# OpenBookReader_v54.net
KiCad netlist of a schematic drawn in EAGLE
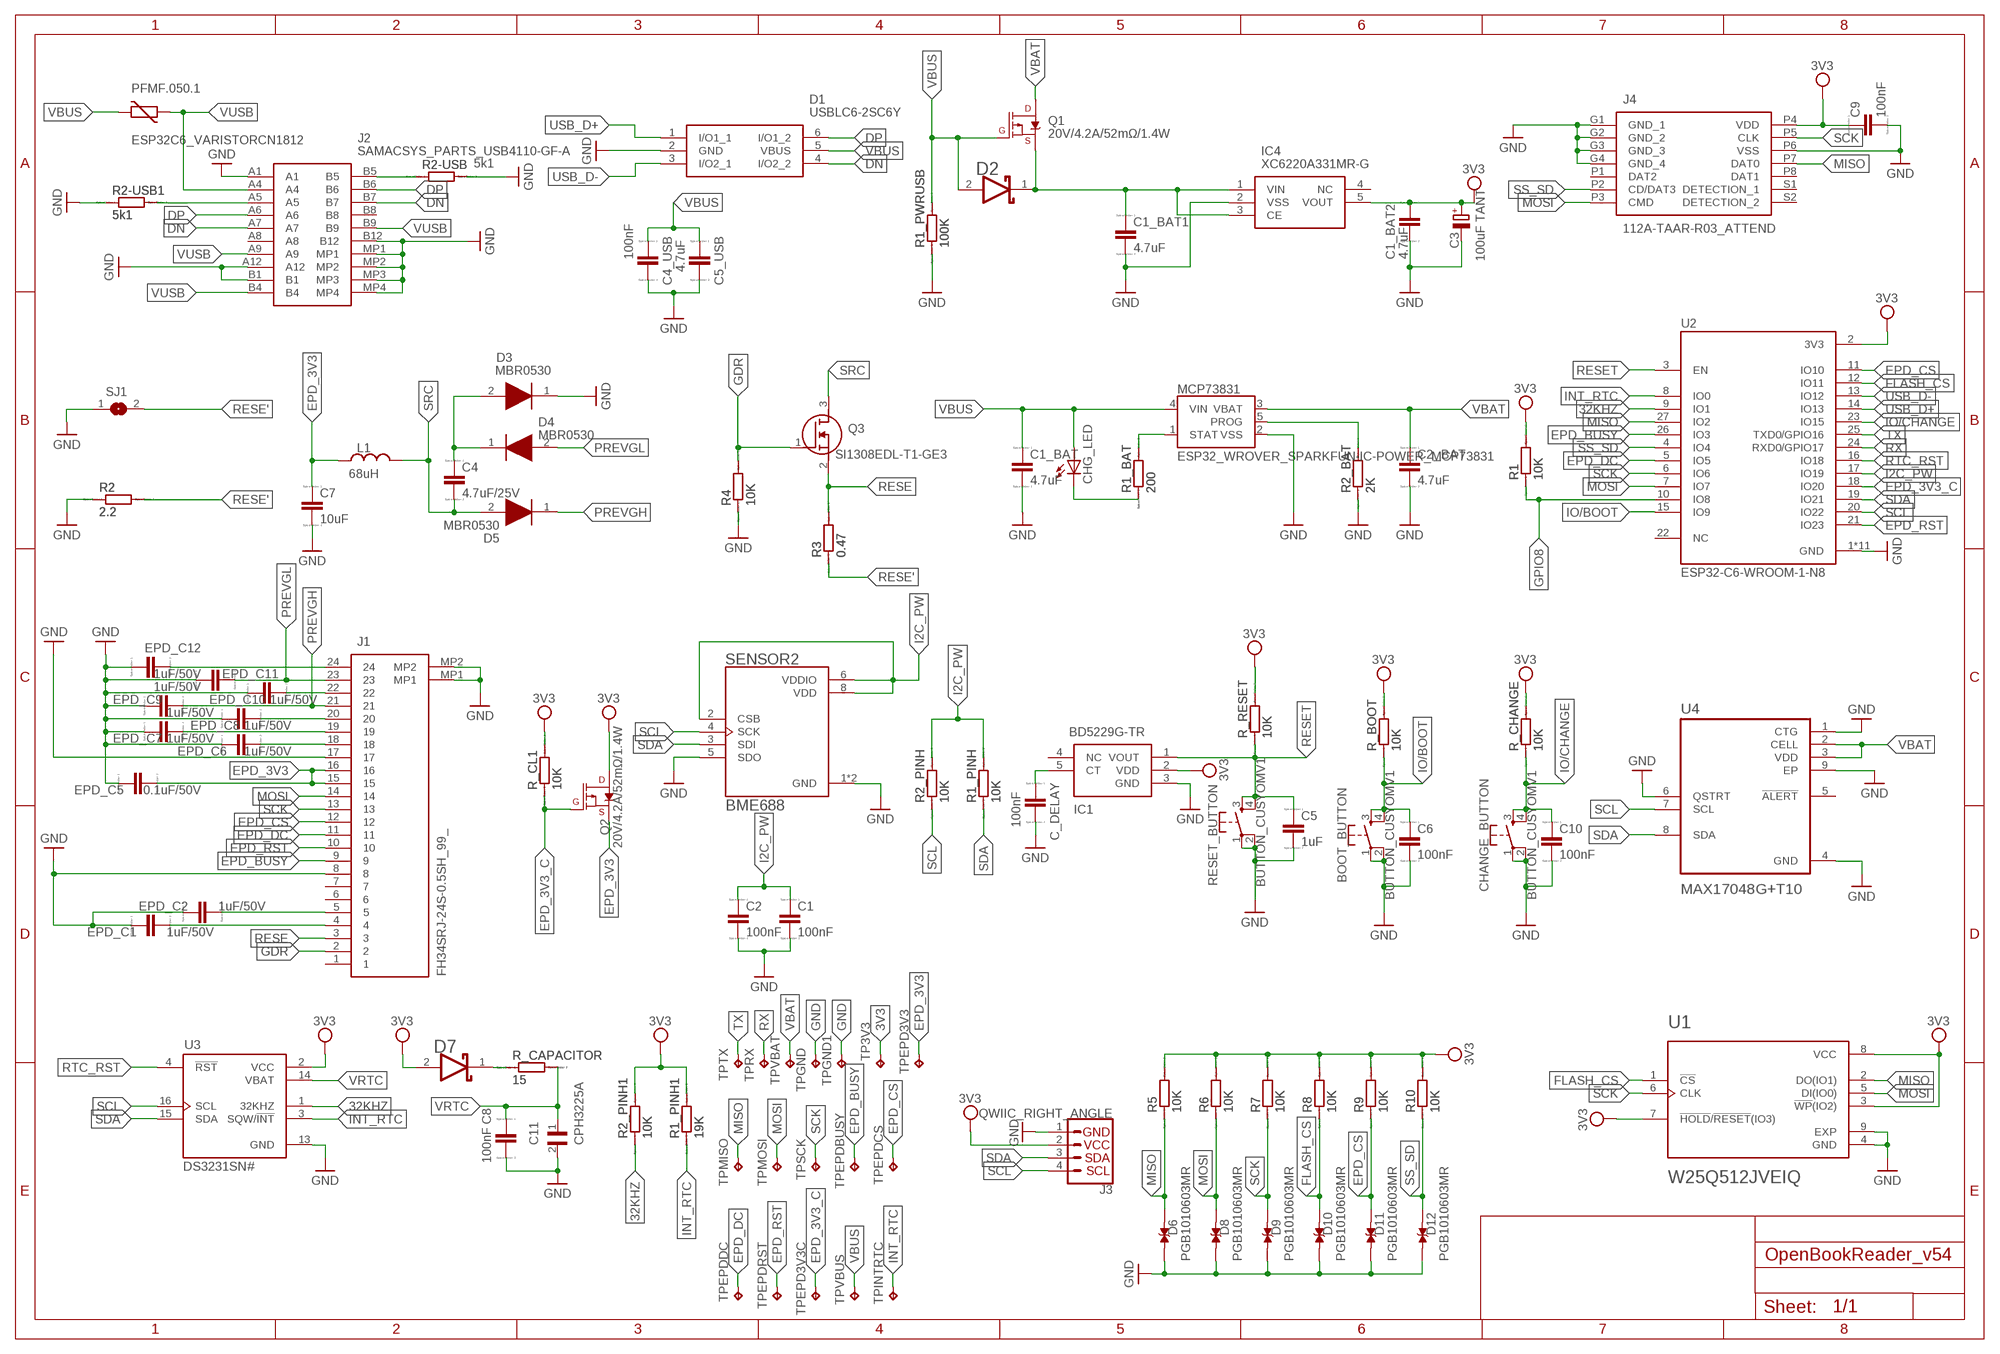
[diagram p0: schematic, sheet 1]

(export (version "E")
  (design (tool "Eeschema 10.0.6"))
  (components
    (comp (ref "BOOT_BUTTON")
      (value "BUTTON_CUSYOMV1")
      (footprint "eagle-import:MYBUTTON")
      (libsource (lib "eagle-import") (part "BUTTON_CUSYOMV1"))
    )
    (comp (ref "C1")
      (value "100nF")
      (footprint "eagle-import:EAGLE-LTSPICE_C0402")
      (libsource (lib "eagle-import") (part "EAGLE-LTSPICE_CC0402"))
    )
    (comp (ref "C1_BAT")
      (value "4.7uF")
      (footprint "eagle-import:EAGLE-LTSPICE_C0402")
      (libsource (lib "eagle-import") (part "EAGLE-LTSPICE_CC0402"))
    )
    (comp (ref "C1_BAT1")
      (value "4.7uF")
      (footprint "eagle-import:EAGLE-LTSPICE_C0402")
      (libsource (lib "eagle-import") (part "EAGLE-LTSPICE_CC0402"))
    )
    (comp (ref "C1_BAT2")
      (value "4.7uF")
      (footprint "eagle-import:EAGLE-LTSPICE_C0402")
      (libsource (lib "eagle-import") (part "EAGLE-LTSPICE_CC0402"))
    )
    (comp (ref "C2")
      (value "100nF")
      (footprint "eagle-import:EAGLE-LTSPICE_C0402")
      (libsource (lib "eagle-import") (part "EAGLE-LTSPICE_CC0402"))
    )
    (comp (ref "C2_BAT")
      (value "4.7uF")
      (footprint "eagle-import:EAGLE-LTSPICE_C0402")
      (libsource (lib "eagle-import") (part "EAGLE-LTSPICE_CC0402"))
    )
    (comp (ref "C3")
      (value "100uF TANT")
      (footprint "eagle-import:RCL_CT3528")
      (libsource (lib "eagle-import") (part "RCL_CPOL-EUCT3528"))
    )
    (comp (ref "C4")
      (value "4.7uF/25V")
      (footprint "eagle-import:EAGLE-LTSPICE_C0402")
      (libsource (lib "eagle-import") (part "EAGLE-LTSPICE_CC0402"))
    )
    (comp (ref "C4_USB")
      (value "100nF")
      (footprint "eagle-import:EAGLE-LTSPICE_C0402")
      (libsource (lib "eagle-import") (part "EAGLE-LTSPICE_CC0402"))
    )
    (comp (ref "C5")
      (value "1uF")
      (footprint "eagle-import:EAGLE-LTSPICE_C0402")
      (libsource (lib "eagle-import") (part "EAGLE-LTSPICE_CC0402"))
    )
    (comp (ref "C5_USB")
      (value "4.7uF")
      (footprint "eagle-import:EAGLE-LTSPICE_C0402")
      (libsource (lib "eagle-import") (part "EAGLE-LTSPICE_CC0402"))
    )
    (comp (ref "C6")
      (value "100nF")
      (footprint "eagle-import:EAGLE-LTSPICE_C0402")
      (libsource (lib "eagle-import") (part "EAGLE-LTSPICE_CC0402"))
    )
    (comp (ref "C7")
      (value "10uF")
      (footprint "eagle-import:EAGLE-LTSPICE_C0402")
      (libsource (lib "eagle-import") (part "EAGLE-LTSPICE_CC0402"))
    )
    (comp (ref "C8")
      (value "100nF")
      (footprint "eagle-import:EAGLE-LTSPICE_C0402")
      (libsource (lib "eagle-import") (part "EAGLE-LTSPICE_CC0402"))
    )
    (comp (ref "C9")
      (value "100nF")
      (footprint "eagle-import:EAGLE-LTSPICE_C0402")
      (libsource (lib "eagle-import") (part "EAGLE-LTSPICE_CC0402"))
    )
    (comp (ref "C10")
      (value "100nF")
      (footprint "eagle-import:EAGLE-LTSPICE_C0402")
      (libsource (lib "eagle-import") (part "EAGLE-LTSPICE_CC0402"))
    )
    (comp (ref "C11")
      (value "CPH3225A")
      (footprint "eagle-import:CAPCP3225X100N")
      (fields (field (name "MF") "Seiko Instruments"))
      (libsource (lib "eagle-import") (part "CPH3225A"))
    )
    (comp (ref "CHANGE_BUTTON")
      (value "BUTTON_CUSYOMV1")
      (footprint "eagle-import:MYBUTTON")
      (libsource (lib "eagle-import") (part "BUTTON_CUSYOMV1"))
    )
    (comp (ref "CHG_LED")
      (value "ADAFRUIT_LEDCHIP-LED0603")
      (footprint "eagle-import:ADAFRUIT_CHIP-LED0603")
      (libsource (lib "eagle-import") (part "ADAFRUIT_LEDCHIP-LED0603"))
    )
    (comp (ref "C_DELAY")
      (value "100nF")
      (footprint "eagle-import:EAGLE-LTSPICE_C0402")
      (libsource (lib "eagle-import") (part "EAGLE-LTSPICE_CC0402"))
    )
    (comp (ref "D1")
      (value "USBLC6-2SC6Y")
      (footprint "eagle-import:SOT95P280X145-6N")
      (fields (field (name "MF") "STMicroelectronics"))
      (libsource (lib "eagle-import") (part "USBLC6-2SC6Y"))
    )
    (comp (ref "D2")
      (value "ESP32_WROVER_AVX---SD0805S020S1R0_AVX_SD0805S020S1R0_0_0AVX_SD0805S020S1R0_0_0")
      (footprint "eagle-import:ESP32_WROVER_AVX---SD0805S020S1R0_AVX_SD0805S020S1R0_0")
      (fields
        (field (name "DIGIKEY_PART_NUMBER") "478-7800-1-ND")
        (field (name "MF") "AVX")
        (field (name "MOUSER_PART_NUMBER") "581-SD0805S020S1R0")
      )
      (libsource (lib "eagle-import") (part "ESP32_WROVER_AVX---SD0805S020S1R0_AVX_SD0805S020S1R0_0_0AVX_SD0805S020S1R0_0_0"))
    )
    (comp (ref "D3")
      (value "MBR0530")
      (footprint "eagle-import:SOD3716X135N")
      (fields (field (name "MF") "ON Semiconductor"))
      (libsource (lib "eagle-import") (part "MBR0530"))
    )
    (comp (ref "D4")
      (value "MBR0530")
      (footprint "eagle-import:SOD3716X135N")
      (fields (field (name "MF") "ON Semiconductor"))
      (libsource (lib "eagle-import") (part "MBR0530"))
    )
    (comp (ref "D5")
      (value "MBR0530")
      (footprint "eagle-import:SOD3716X135N")
      (fields (field (name "MF") "ON Semiconductor"))
      (libsource (lib "eagle-import") (part "MBR0530"))
    )
    (comp (ref "D6")
      (value "PGB1010603MR")
      (footprint "eagle-import:DIOC1608X36N")
      (fields (field (name "MF") "Littelfuse Inc."))
      (libsource (lib "eagle-import") (part "PGB1010603MR"))
    )
    (comp (ref "D7")
      (value "ESP32_WROVER_AVX---SD0805S020S1R0_AVX_SD0805S020S1R0_0_0AVX_SD0805S020S1R0_0_0")
      (footprint "eagle-import:ESP32_WROVER_AVX---SD0805S020S1R0_AVX_SD0805S020S1R0_0")
      (fields
        (field (name "DIGIKEY_PART_NUMBER") "478-7800-1-ND")
        (field (name "MF") "AVX")
        (field (name "MOUSER_PART_NUMBER") "581-SD0805S020S1R0")
      )
      (libsource (lib "eagle-import") (part "ESP32_WROVER_AVX---SD0805S020S1R0_AVX_SD0805S020S1R0_0_0AVX_SD0805S020S1R0_0_0"))
    )
    (comp (ref "D8")
      (value "PGB1010603MR")
      (footprint "eagle-import:DIOC1608X36N")
      (fields (field (name "MF") "Littelfuse Inc."))
      (libsource (lib "eagle-import") (part "PGB1010603MR"))
    )
    (comp (ref "D9")
      (value "PGB1010603MR")
      (footprint "eagle-import:DIOC1608X36N")
      (fields (field (name "MF") "Littelfuse Inc."))
      (libsource (lib "eagle-import") (part "PGB1010603MR"))
    )
    (comp (ref "D10")
      (value "PGB1010603MR")
      (footprint "eagle-import:DIOC1608X36N")
      (fields (field (name "MF") "Littelfuse Inc."))
      (libsource (lib "eagle-import") (part "PGB1010603MR"))
    )
    (comp (ref "D11")
      (value "PGB1010603MR")
      (footprint "eagle-import:DIOC1608X36N")
      (fields (field (name "MF") "Littelfuse Inc."))
      (libsource (lib "eagle-import") (part "PGB1010603MR"))
    )
    (comp (ref "D12")
      (value "PGB1010603MR")
      (footprint "eagle-import:DIOC1608X36N")
      (fields (field (name "MF") "Littelfuse Inc."))
      (libsource (lib "eagle-import") (part "PGB1010603MR"))
    )
    (comp (ref "EPD_C1")
      (value "1uF/50V")
      (footprint "eagle-import:EAGLE-LTSPICE_C0402")
      (libsource (lib "eagle-import") (part "EAGLE-LTSPICE_CC0402"))
    )
    (comp (ref "EPD_C2")
      (value "1uF/50V")
      (footprint "eagle-import:EAGLE-LTSPICE_C0402")
      (libsource (lib "eagle-import") (part "EAGLE-LTSPICE_CC0402"))
    )
    (comp (ref "EPD_C5")
      (value "0.1uF/50V")
      (footprint "eagle-import:EAGLE-LTSPICE_C0402")
      (libsource (lib "eagle-import") (part "EAGLE-LTSPICE_CC0402"))
    )
    (comp (ref "EPD_C6")
      (value "1uF/50V")
      (footprint "eagle-import:EAGLE-LTSPICE_C0402")
      (libsource (lib "eagle-import") (part "EAGLE-LTSPICE_CC0402"))
    )
    (comp (ref "EPD_C7")
      (value "1uF/50V")
      (footprint "eagle-import:EAGLE-LTSPICE_C0402")
      (libsource (lib "eagle-import") (part "EAGLE-LTSPICE_CC0402"))
    )
    (comp (ref "EPD_C8")
      (value "1uF/50V")
      (footprint "eagle-import:EAGLE-LTSPICE_C0402")
      (libsource (lib "eagle-import") (part "EAGLE-LTSPICE_CC0402"))
    )
    (comp (ref "EPD_C9")
      (value "1uF/50V")
      (footprint "eagle-import:EAGLE-LTSPICE_C0402")
      (libsource (lib "eagle-import") (part "EAGLE-LTSPICE_CC0402"))
    )
    (comp (ref "EPD_C10")
      (value "1uF/50V")
      (footprint "eagle-import:EAGLE-LTSPICE_C0402")
      (libsource (lib "eagle-import") (part "EAGLE-LTSPICE_CC0402"))
    )
    (comp (ref "EPD_C11")
      (value "1uF/50V")
      (footprint "eagle-import:EAGLE-LTSPICE_C0402")
      (libsource (lib "eagle-import") (part "EAGLE-LTSPICE_CC0402"))
    )
    (comp (ref "EPD_C12")
      (value "1uF/50V")
      (footprint "eagle-import:EAGLE-LTSPICE_C0402")
      (libsource (lib "eagle-import") (part "EAGLE-LTSPICE_CC0402"))
    )
    (comp (ref "IC1")
      (value "BD5229G-TR")
      (footprint "eagle-import:SOT95P280X125-5N")
      (fields (field (name "MOUSER_PART_NUMBER") "755-BD5229G-TR"))
      (libsource (lib "eagle-import") (part "BD5229G-TR"))
    )
    (comp (ref "IC4")
      (value "XC6220A331MR-G")
      (footprint "eagle-import:SOT95P280X120-5N")
      (fields (field (name "MOUSER_PART_NUMBER") "865-XC6220A331MR-G"))
      (libsource (lib "eagle-import") (part "XC6220A331MR-G"))
    )
    (comp (ref "J1")
      (value "FH34SRJ-24S-0.5SH_99_")
      (footprint "eagle-import:FH34SRJ24S05SH99")
      (fields
        (field (name "MANUFACTURER_PART_NUMBER") "FH34SRJ-24S-0.5SH(99)")
        (field (name "MOUSER_PART_NUMBER") "798-FH34SRJ24S05SH99")
      )
      (libsource (lib "eagle-import") (part "FH34SRJ-24S-0.5SH_99_"))
    )
    (comp (ref "J2")
      (value "SAMACSYS_PARTS_USB4110-GF-A")
      (footprint "eagle-import:SAMACSYS_PARTS_USB4110GFA")
      (fields
        (field (name "MANUFACTURER_PART_NUMBER") "USB4110-GF-A")
        (field (name "MOUSER_PART_NUMBER") "640-USB4110-GF-A")
      )
      (libsource (lib "eagle-import") (part "SAMACSYS_PARTS_USB4110-GF-A"))
    )
    (comp (ref "J3")
      (value "QWIIC_RIGHT_ANGLE")
      (footprint "eagle-import:JST04_1MM_RA")
      (libsource (lib "eagle-import") (part "QWIIC_CONNECTORJS-1MM"))
    )
    (comp (ref "J4")
      (value "112A-TAAR-R03_ATTEND")
      (footprint "eagle-import:112ATAARR03ATTEND")
      (fields (field (name "MANUFACTURER_PART_NUMBER") "112A-TAAR-R03 ATTEND"))
      (libsource (lib "eagle-import") (part "112A-TAAR-R03_ATTEND"))
    )
    (comp (ref "L1")
      (value "68uH")
      (footprint "eagle-import:INDC1006X60N")
      (libsource (lib "eagle-import") (part "INDUCTORCHIP-0402(1006-METRIC)_"))
    )
    (comp (ref "MCP73831")
      (value "ESP32_WROVER_SPARKFUN-IC-POWER_MCP73831")
      (footprint "eagle-import:ESP32_WROVER_SPARKFUN-IC-POWER_SOT23-5")
      (libsource (lib "eagle-import") (part "ESP32_WROVER_SPARKFUN-IC-POWER_MCP73831"))
    )
    (comp (ref "PFMF.050.1")
      (value "ESP32C6_VARISTORCN1812")
      (footprint "eagle-import:ESP32C6_VARISTOR_CT_CN1812")
      (libsource (lib "eagle-import") (part "ESP32C6_VARISTORCN1812"))
    )
    (comp (ref "Q1")
      (value "20V/4.2A/52mΩ/1.4W")
      (footprint "eagle-import:ESP32_WROVER_SPARKFUN-DISCRETESEMI_SOT23-3")
      (libsource (lib "eagle-import") (part "ESP32_WROVER_SPARKFUN-DISCRETESEMI_MOSFET_PCH-DMG2305UX-7"))
    )
    (comp (ref "Q2")
      (value "20V/4.2A/52mΩ/1.4W")
      (footprint "eagle-import:ESP32_WROVER_SPARKFUN-DISCRETESEMI_SOT23-3")
      (libsource (lib "eagle-import") (part "ESP32_WROVER_SPARKFUN-DISCRETESEMI_MOSFET_PCH-DMG2305UX-7"))
    )
    (comp (ref "Q3")
      (value "SI1308EDL-T1-GE3")
      (footprint "eagle-import:SOT65P210X110-3N")
      (fields (field (name "MF") "Vishay Siliconix"))
      (libsource (lib "eagle-import") (part "SI1308EDL-T1-GE3"))
    )
    (comp (ref "R1")
      (value "10K")
      (footprint "eagle-import:ESP32_WROVER_EAGLE-LTSPICE_R0402")
      (libsource (lib "eagle-import") (part "ESP32_WROVER_EAGLE-LTSPICE_RR0402"))
    )
    (comp (ref "R1_BAT")
      (value "200")
      (footprint "eagle-import:ESP32_WROVER_EAGLE-LTSPICE_R0402")
      (libsource (lib "eagle-import") (part "ESP32_WROVER_EAGLE-LTSPICE_RR0402"))
    )
    (comp (ref "R1_PINH")
      (value "10K")
      (footprint "eagle-import:ESP32_WROVER_EAGLE-LTSPICE_R0402")
      (libsource (lib "eagle-import") (part "ESP32_WROVER_EAGLE-LTSPICE_RR0402"))
    )
    (comp (ref "R1_PINH1")
      (value "19K")
      (footprint "eagle-import:ESP32_WROVER_EAGLE-LTSPICE_R0402")
      (libsource (lib "eagle-import") (part "ESP32_WROVER_EAGLE-LTSPICE_RR0402"))
    )
    (comp (ref "R1_PWRUSB")
      (value "100K")
      (footprint "eagle-import:ESP32_WROVER_EAGLE-LTSPICE_R0402")
      (libsource (lib "eagle-import") (part "ESP32_WROVER_EAGLE-LTSPICE_RR0402"))
    )
    (comp (ref "R2")
      (value "2.2")
      (footprint "eagle-import:ESP32_WROVER_EAGLE-LTSPICE_R0402")
      (libsource (lib "eagle-import") (part "ESP32_WROVER_EAGLE-LTSPICE_RR0402"))
    )
    (comp (ref "R2-USB")
      (value "5k1")
      (footprint "eagle-import:ESP32_WROVER_EAGLE-LTSPICE_R0402")
      (libsource (lib "eagle-import") (part "ESP32_WROVER_EAGLE-LTSPICE_RR0402"))
    )
    (comp (ref "R2-USB1")
      (value "5k1")
      (footprint "eagle-import:ESP32_WROVER_EAGLE-LTSPICE_R0402")
      (libsource (lib "eagle-import") (part "ESP32_WROVER_EAGLE-LTSPICE_RR0402"))
    )
    (comp (ref "R2_BAT")
      (value "2K")
      (footprint "eagle-import:ESP32_WROVER_EAGLE-LTSPICE_R0402")
      (libsource (lib "eagle-import") (part "ESP32_WROVER_EAGLE-LTSPICE_RR0402"))
    )
    (comp (ref "R2_PINH")
      (value "10K")
      (footprint "eagle-import:ESP32_WROVER_EAGLE-LTSPICE_R0402")
      (libsource (lib "eagle-import") (part "ESP32_WROVER_EAGLE-LTSPICE_RR0402"))
    )
    (comp (ref "R2_PINH1")
      (value "10K")
      (footprint "eagle-import:ESP32_WROVER_EAGLE-LTSPICE_R0402")
      (libsource (lib "eagle-import") (part "ESP32_WROVER_EAGLE-LTSPICE_RR0402"))
    )
    (comp (ref "R3")
      (value "0.47")
      (footprint "eagle-import:ESP32_WROVER_EAGLE-LTSPICE_R0402")
      (libsource (lib "eagle-import") (part "ESP32_WROVER_EAGLE-LTSPICE_RR0402"))
    )
    (comp (ref "R4")
      (value "10K")
      (footprint "eagle-import:ESP32_WROVER_EAGLE-LTSPICE_R0402")
      (libsource (lib "eagle-import") (part "ESP32_WROVER_EAGLE-LTSPICE_RR0402"))
    )
    (comp (ref "R5")
      (value "10K")
      (footprint "eagle-import:ESP32_WROVER_EAGLE-LTSPICE_R0402")
      (libsource (lib "eagle-import") (part "ESP32_WROVER_EAGLE-LTSPICE_RR0402"))
    )
    (comp (ref "R6")
      (value "10K")
      (footprint "eagle-import:ESP32_WROVER_EAGLE-LTSPICE_R0402")
      (libsource (lib "eagle-import") (part "ESP32_WROVER_EAGLE-LTSPICE_RR0402"))
    )
    (comp (ref "R7")
      (value "10K")
      (footprint "eagle-import:ESP32_WROVER_EAGLE-LTSPICE_R0402")
      (libsource (lib "eagle-import") (part "ESP32_WROVER_EAGLE-LTSPICE_RR0402"))
    )
    (comp (ref "R8")
      (value "10K")
      (footprint "eagle-import:ESP32_WROVER_EAGLE-LTSPICE_R0402")
      (libsource (lib "eagle-import") (part "ESP32_WROVER_EAGLE-LTSPICE_RR0402"))
    )
    (comp (ref "R9")
      (value "10K")
      (footprint "eagle-import:ESP32_WROVER_EAGLE-LTSPICE_R0402")
      (libsource (lib "eagle-import") (part "ESP32_WROVER_EAGLE-LTSPICE_RR0402"))
    )
    (comp (ref "R10")
      (value "10K")
      (footprint "eagle-import:ESP32_WROVER_EAGLE-LTSPICE_R0402")
      (libsource (lib "eagle-import") (part "ESP32_WROVER_EAGLE-LTSPICE_RR0402"))
    )
    (comp (ref "RESET_BUTTON")
      (value "BUTTON_CUSYOMV1")
      (footprint "eagle-import:MYBUTTON")
      (libsource (lib "eagle-import") (part "BUTTON_CUSYOMV1"))
    )
    (comp (ref "R_BOOT")
      (value "10K")
      (footprint "eagle-import:ESP32_WROVER_EAGLE-LTSPICE_R0402")
      (libsource (lib "eagle-import") (part "ESP32_WROVER_EAGLE-LTSPICE_RR0402"))
    )
    (comp (ref "R_CAPACITOR")
      (value "15")
      (footprint "eagle-import:ESP32_WROVER_EAGLE-LTSPICE_R0402")
      (libsource (lib "eagle-import") (part "ESP32_WROVER_EAGLE-LTSPICE_RR0402"))
    )
    (comp (ref "R_CHANGE")
      (value "10K")
      (footprint "eagle-import:ESP32_WROVER_EAGLE-LTSPICE_R0402")
      (libsource (lib "eagle-import") (part "ESP32_WROVER_EAGLE-LTSPICE_RR0402"))
    )
    (comp (ref "R_CL1")
      (value "10K")
      (footprint "eagle-import:ESP32_WROVER_EAGLE-LTSPICE_R0402")
      (libsource (lib "eagle-import") (part "ESP32_WROVER_EAGLE-LTSPICE_RR0402"))
    )
    (comp (ref "R_RESET")
      (value "10K")
      (footprint "eagle-import:ESP32_WROVER_EAGLE-LTSPICE_R0402")
      (libsource (lib "eagle-import") (part "ESP32_WROVER_EAGLE-LTSPICE_RR0402"))
    )
    (comp (ref "SENSOR2")
      (value "BME688")
      (footprint "eagle-import:ESP32_WROVER_BME680_PSON80P300X300X100-8N")
      (fields (field (name "MF") "Bosch Sensortec") (field (name "MP") "BME680"))
      (libsource (lib "eagle-import") (part "ESP32_WROVER_BME680_BME680"))
    )
    (comp (ref "SJ1") (value "SJ") (footprint "eagle-import:SJ") (libsource (lib "eagle-import") (part "SJ")))
    (comp (ref "TP3V3")
      (value "TPTP20R")
      (footprint "eagle-import:TP20R")
      (libsource (lib "eagle-import") (part "TPTP20R"))
    )
    (comp (ref "TPEPD3V3")
      (value "TPTP20R")
      (footprint "eagle-import:TP20R")
      (libsource (lib "eagle-import") (part "TPTP20R"))
    )
    (comp (ref "TPEPD3V3C")
      (value "TPTP20R")
      (footprint "eagle-import:TP20R")
      (libsource (lib "eagle-import") (part "TPTP20R"))
    )
    (comp (ref "TPEPDBUSY")
      (value "TPTP20R")
      (footprint "eagle-import:TP20R")
      (libsource (lib "eagle-import") (part "TPTP20R"))
    )
    (comp (ref "TPEPDCS")
      (value "TPTP20R")
      (footprint "eagle-import:TP20R")
      (libsource (lib "eagle-import") (part "TPTP20R"))
    )
    (comp (ref "TPEPDDC")
      (value "TPTP20R")
      (footprint "eagle-import:TP20R")
      (libsource (lib "eagle-import") (part "TPTP20R"))
    )
    (comp (ref "TPEPDRST")
      (value "TPTP20R")
      (footprint "eagle-import:TP20R")
      (libsource (lib "eagle-import") (part "TPTP20R"))
    )
    (comp (ref "TPGND")
      (value "TPTP20R")
      (footprint "eagle-import:TP20R")
      (libsource (lib "eagle-import") (part "TPTP20R"))
    )
    (comp (ref "TPGND1")
      (value "TPTP20R")
      (footprint "eagle-import:TP20R")
      (libsource (lib "eagle-import") (part "TPTP20R"))
    )
    (comp (ref "TPINTRTC")
      (value "TPTP20R")
      (footprint "eagle-import:TP20R")
      (libsource (lib "eagle-import") (part "TPTP20R"))
    )
    (comp (ref "TPMISO")
      (value "TPTP20R")
      (footprint "eagle-import:TP20R")
      (libsource (lib "eagle-import") (part "TPTP20R"))
    )
    (comp (ref "TPMOSI")
      (value "TPTP20R")
      (footprint "eagle-import:TP20R")
      (libsource (lib "eagle-import") (part "TPTP20R"))
    )
    (comp (ref "TPRX")
      (value "TPTP20R")
      (footprint "eagle-import:TP20R")
      (libsource (lib "eagle-import") (part "TPTP20R"))
    )
    (comp (ref "TPSCK")
      (value "TPTP20R")
      (footprint "eagle-import:TP20R")
      (libsource (lib "eagle-import") (part "TPTP20R"))
    )
    (comp (ref "TPTX")
      (value "TPTP20R")
      (footprint "eagle-import:TP20R")
      (libsource (lib "eagle-import") (part "TPTP20R"))
    )
    (comp (ref "TPVBAT")
      (value "TPTP20R")
      (footprint "eagle-import:TP20R")
      (libsource (lib "eagle-import") (part "TPTP20R"))
    )
    (comp (ref "TPVBUS")
      (value "TPTP20R")
      (footprint "eagle-import:TP20R")
      (libsource (lib "eagle-import") (part "TPTP20R"))
    )
    (comp (ref "U1")
      (value "W25Q512JVEIQ")
      (footprint "eagle-import:SON127P600X800X80-9N")
      (fields (field (name "MF") "Winbond Electronics"))
      (libsource (lib "eagle-import") (part "W25Q512JVEIQ"))
    )
    (comp (ref "U2")
      (value "ESP32-C6-WROOM-1-N8")
      (footprint "eagle-import:XCVR_ESP32-C6-WROOM-1-N8")
      (fields (field (name "MF") "Espressif Systems"))
      (libsource (lib "eagle-import") (part "ESP32-C6-WROOM-1-N8"))
    )
    (comp (ref "U3")
      (value "DS3231SN#")
      (footprint "eagle-import:SOIC127P1032X265-16N")
      (fields (field (name "MF") "Analog Devices"))
      (libsource (lib "eagle-import") (part "DS3231SN#"))
    )
    (comp (ref "U4")
      (value "MAX17048G+T10")
      (footprint "eagle-import:SON50P200X200X80-9N")
      (fields (field (name "MF") "Analog Devices"))
      (libsource (lib "eagle-import") (part "MAX17048G+T10"))
    )
  )
  (nets
    (net (code "1") (name "3V3") (class "Default")
      (node (ref "C1_BAT2") (pin "1") (pinfunction "1_1") (pintype "passive"))
      (node (ref "C3") (pin "+") (pinfunction "+_+") (pintype "passive"))
      (node (ref "C9") (pin "1") (pinfunction "1_1") (pintype "passive"))
      (node (ref "D7") (pin "2") (pinfunction "ANODE_2") (pintype "bidirectional"))
      (node (ref "IC1") (pin "2") (pinfunction "VDD_2") (pintype "bidirectional"))
      (node (ref "IC4") (pin "5") (pinfunction "VOUT_5") (pintype "bidirectional"))
      (node (ref "J3") (pin "2") (pinfunction "2_2") (pintype "power_in"))
      (node (ref "J4") (pin "P4") (pinfunction "VDD_P4") (pintype "bidirectional"))
      (node (ref "Q2") (pin "3") (pinfunction "D_3") (pintype "bidirectional"))
      (node (ref "R1") (pin "2") (pinfunction "2_2") (pintype "passive"))
      (node (ref "R10") (pin "2") (pinfunction "2_2") (pintype "passive"))
      (node (ref "R1_PINH1") (pin "2") (pinfunction "2_2") (pintype "passive"))
      (node (ref "R2_PINH1") (pin "2") (pinfunction "2_2") (pintype "passive"))
      (node (ref "R5") (pin "2") (pinfunction "2_2") (pintype "passive"))
      (node (ref "R6") (pin "2") (pinfunction "2_2") (pintype "passive"))
      (node (ref "R7") (pin "2") (pinfunction "2_2") (pintype "passive"))
      (node (ref "R8") (pin "2") (pinfunction "2_2") (pintype "passive"))
      (node (ref "R9") (pin "2") (pinfunction "2_2") (pintype "passive"))
      (node (ref "R_BOOT") (pin "2") (pinfunction "2_2") (pintype "passive"))
      (node (ref "R_CHANGE") (pin "2") (pinfunction "2_2") (pintype "passive"))
      (node (ref "R_CL1") (pin "2") (pinfunction "2_2") (pintype "passive"))
      (node (ref "R_RESET") (pin "2") (pinfunction "2_2") (pintype "passive"))
      (node (ref "TP3V3") (pin "TP") (pinfunction "TP_TP") (pintype "input"))
      (node (ref "U1") (pin "3") (pinfunction "~{WP}(IO2)_3") (pintype "bidirectional"))
      (node (ref "U1") (pin "7") (pinfunction "~{HOLD}/~{RESET}(IO3)_7") (pintype "bidirectional"))
      (node (ref "U1") (pin "8") (pinfunction "VCC_8") (pintype "power_in"))
      (node (ref "U2") (pin "2") (pinfunction "3V3_2") (pintype "power_in"))
      (node (ref "U3") (pin "2") (pinfunction "VCC_2") (pintype "power_in"))
    )
    (net (code "2") (name "32KHZ") (class "Default")
      (node (ref "R2_PINH1") (pin "1") (pinfunction "1_1") (pintype "passive"))
      (node (ref "U2") (pin "9") (pinfunction "IO1_9") (pintype "bidirectional"))
      (node (ref "U3") (pin "1") (pinfunction "32KHZ_1") (pintype "output"))
    )
    (net (code "3") (name "DN") (class "Default")
      (node (ref "D1") (pin "4") (pinfunction "I/O2_2_4") (pintype "bidirectional"))
      (node (ref "J2") (pin "A7") (pinfunction "A7_A7") (pintype "bidirectional"))
      (node (ref "J2") (pin "B7") (pinfunction "B7_B7") (pintype "bidirectional"))
    )
    (net (code "4") (name "DP") (class "Default")
      (node (ref "D1") (pin "6") (pinfunction "I/O1_2_6") (pintype "bidirectional"))
      (node (ref "J2") (pin "A6") (pinfunction "A6_A6") (pintype "bidirectional"))
      (node (ref "J2") (pin "B6") (pinfunction "B6_B6") (pintype "bidirectional"))
    )
    (net (code "5") (name "EPD_3V3") (class "Default")
      (node (ref "C7") (pin "1") (pinfunction "1_1") (pintype "passive"))
      (node (ref "EPD_C5") (pin "2") (pinfunction "2_2") (pintype "passive"))
      (node (ref "J1") (pin "15") (pinfunction "15_15") (pintype "bidirectional"))
      (node (ref "J1") (pin "16") (pinfunction "16_16") (pintype "bidirectional"))
      (node (ref "L1") (pin "1") (pinfunction "1_1") (pintype "passive"))
      (node (ref "Q2") (pin "2") (pinfunction "S_2") (pintype "bidirectional"))
      (node (ref "TPEPD3V3") (pin "TP") (pinfunction "TP_TP") (pintype "input"))
    )
    (net (code "6") (name "EPD_3V3_C") (class "Default")
      (node (ref "Q2") (pin "1") (pinfunction "G_1") (pintype "bidirectional"))
      (node (ref "R_CL1") (pin "1") (pinfunction "1_1") (pintype "passive"))
      (node (ref "TPEPD3V3C") (pin "TP") (pinfunction "TP_TP") (pintype "input"))
      (node (ref "U2") (pin "18") (pinfunction "IO20_18") (pintype "bidirectional"))
    )
    (net (code "7") (name "EPD_BUSY") (class "Default")
      (node (ref "J1") (pin "9") (pinfunction "9_9") (pintype "bidirectional"))
      (node (ref "TPEPDBUSY") (pin "TP") (pinfunction "TP_TP") (pintype "input"))
      (node (ref "U2") (pin "26") (pinfunction "IO3_26") (pintype "bidirectional"))
    )
    (net (code "8") (name "EPD_CS") (class "Default")
      (node (ref "D11") (pin "2") (pinfunction "2_2") (pintype "passive"))
      (node (ref "J1") (pin "12") (pinfunction "12_12") (pintype "bidirectional"))
      (node (ref "R9") (pin "1") (pinfunction "1_1") (pintype "passive"))
      (node (ref "TPEPDCS") (pin "TP") (pinfunction "TP_TP") (pintype "input"))
      (node (ref "U2") (pin "11") (pinfunction "IO10_11") (pintype "bidirectional"))
    )
    (net (code "9") (name "EPD_DC") (class "Default")
      (node (ref "J1") (pin "11") (pinfunction "11_11") (pintype "bidirectional"))
      (node (ref "TPEPDDC") (pin "TP") (pinfunction "TP_TP") (pintype "input"))
      (node (ref "U2") (pin "5") (pinfunction "IO5_5") (pintype "bidirectional"))
    )
    (net (code "10") (name "EPD_RST") (class "Default")
      (node (ref "J1") (pin "10") (pinfunction "10_10") (pintype "bidirectional"))
      (node (ref "TPEPDRST") (pin "TP") (pinfunction "TP_TP") (pintype "input"))
      (node (ref "U2") (pin "21") (pinfunction "IO23_21") (pintype "bidirectional"))
    )
    (net (code "11") (name "FLASH_CS") (class "Default")
      (node (ref "D10") (pin "2") (pinfunction "2_2") (pintype "passive"))
      (node (ref "R8") (pin "1") (pinfunction "1_1") (pintype "passive"))
      (node (ref "U1") (pin "1") (pinfunction "~{CS}_1") (pintype "input"))
      (node (ref "U2") (pin "12") (pinfunction "IO11_12") (pintype "bidirectional"))
    )
    (net (code "12") (name "GDR") (class "Default")
      (node (ref "J1") (pin "2") (pinfunction "2_2") (pintype "bidirectional"))
      (node (ref "Q3") (pin "1") (pinfunction "G_1") (pintype "bidirectional"))
      (node (ref "R4") (pin "2") (pinfunction "2_2") (pintype "passive"))
    )
    (net (code "13") (name "GND") (class "Default")
      (node (ref "BOOT_BUTTON") (pin "1") (pinfunction "1_1") (pintype "passive"))
      (node (ref "BOOT_BUTTON") (pin "2") (pinfunction "2_2") (pintype "passive"))
      (node (ref "C1") (pin "2") (pinfunction "2_2") (pintype "passive"))
      (node (ref "C10") (pin "2") (pinfunction "2_2") (pintype "passive"))
      (node (ref "C11") (pin "2") (pinfunction "2_2") (pintype "passive"))
      (node (ref "C1_BAT") (pin "2") (pinfunction "2_2") (pintype "passive"))
      (node (ref "C1_BAT1") (pin "2") (pinfunction "2_2") (pintype "passive"))
      (node (ref "C1_BAT2") (pin "2") (pinfunction "2_2") (pintype "passive"))
      (node (ref "C2") (pin "2") (pinfunction "2_2") (pintype "passive"))
      (node (ref "C2_BAT") (pin "2") (pinfunction "2_2") (pintype "passive"))
      (node (ref "C3") (pin "-") (pinfunction "-_-") (pintype "passive"))
      (node (ref "C4_USB") (pin "2") (pinfunction "2_2") (pintype "passive"))
      (node (ref "C5") (pin "2") (pinfunction "2_2") (pintype "passive"))
      (node (ref "C5_USB") (pin "2") (pinfunction "2_2") (pintype "passive"))
      (node (ref "C6") (pin "2") (pinfunction "2_2") (pintype "passive"))
      (node (ref "C7") (pin "2") (pinfunction "2_2") (pintype "passive"))
      (node (ref "C8") (pin "2") (pinfunction "2_2") (pintype "passive"))
      (node (ref "C9") (pin "2") (pinfunction "2_2") (pintype "passive"))
      (node (ref "CHANGE_BUTTON") (pin "1") (pinfunction "1_1") (pintype "passive"))
      (node (ref "CHANGE_BUTTON") (pin "2") (pinfunction "2_2") (pintype "passive"))
      (node (ref "C_DELAY") (pin "2") (pinfunction "2_2") (pintype "passive"))
      (node (ref "D1") (pin "2") (pinfunction "GND_2") (pintype "bidirectional"))
      (node (ref "D10") (pin "1") (pinfunction "1_1") (pintype "passive"))
      (node (ref "D11") (pin "1") (pinfunction "1_1") (pintype "passive"))
      (node (ref "D12") (pin "1") (pinfunction "1_1") (pintype "passive"))
      (node (ref "D3") (pin "1") (pinfunction "K_1") (pintype "bidirectional"))
      (node (ref "D6") (pin "1") (pinfunction "1_1") (pintype "passive"))
      (node (ref "D8") (pin "1") (pinfunction "1_1") (pintype "passive"))
      (node (ref "D9") (pin "1") (pinfunction "1_1") (pintype "passive"))
      (node (ref "EPD_C1") (pin "1") (pinfunction "1_1") (pintype "passive"))
      (node (ref "EPD_C10") (pin "1") (pinfunction "1_1") (pintype "passive"))
      (node (ref "EPD_C11") (pin "1") (pinfunction "1_1") (pintype "passive"))
      (node (ref "EPD_C12") (pin "1") (pinfunction "1_1") (pintype "passive"))
      (node (ref "EPD_C2") (pin "1") (pinfunction "1_1") (pintype "passive"))
      (node (ref "EPD_C5") (pin "1") (pinfunction "1_1") (pintype "passive"))
      (node (ref "EPD_C6") (pin "1") (pinfunction "1_1") (pintype "passive"))
      (node (ref "EPD_C7") (pin "1") (pinfunction "1_1") (pintype "passive"))
      (node (ref "EPD_C8") (pin "1") (pinfunction "1_1") (pintype "passive"))
      (node (ref "EPD_C9") (pin "1") (pinfunction "1_1") (pintype "passive"))
      (node (ref "IC1") (pin "3") (pinfunction "GND_3") (pintype "bidirectional"))
      (node (ref "IC4") (pin "2") (pinfunction "VSS_2") (pintype "bidirectional"))
      (node (ref "J1") (pin "17") (pinfunction "17_17") (pintype "bidirectional"))
      (node (ref "J1") (pin "8") (pinfunction "8_8") (pintype "bidirectional"))
      (node (ref "J1") (pin "MP1") (pinfunction "MP1_MP1") (pintype "bidirectional"))
      (node (ref "J1") (pin "MP2") (pinfunction "MP2_MP2") (pintype "bidirectional"))
      (node (ref "J2") (pin "A1") (pinfunction "A1_A1") (pintype "bidirectional"))
      (node (ref "J2") (pin "A12") (pinfunction "A12_A12") (pintype "bidirectional"))
      (node (ref "J2") (pin "B1") (pinfunction "B1_B1") (pintype "bidirectional"))
      (node (ref "J2") (pin "B12") (pinfunction "B12_B12") (pintype "bidirectional"))
      (node (ref "J2") (pin "MP1") (pinfunction "MP1_MP1") (pintype "bidirectional"))
      (node (ref "J2") (pin "MP2") (pinfunction "MP2_MP2") (pintype "bidirectional"))
      (node (ref "J2") (pin "MP3") (pinfunction "MP3_MP3") (pintype "bidirectional"))
      (node (ref "J2") (pin "MP4") (pinfunction "MP4_MP4") (pintype "bidirectional"))
      (node (ref "J3") (pin "1") (pinfunction "1_1") (pintype "power_in"))
      (node (ref "J4") (pin "G1") (pinfunction "GND_1_G1") (pintype "bidirectional"))
      (node (ref "J4") (pin "G2") (pinfunction "GND_2_G2") (pintype "bidirectional"))
      (node (ref "J4") (pin "G3") (pinfunction "GND_3_G3") (pintype "bidirectional"))
      (node (ref "J4") (pin "G4") (pinfunction "GND_4_G4") (pintype "bidirectional"))
      (node (ref "J4") (pin "P6") (pinfunction "VSS_P6") (pintype "bidirectional"))
      (node (ref "MCP73831") (pin "2") (pinfunction "VSS_2") (pintype "power_in"))
      (node (ref "R1_PWRUSB") (pin "1") (pinfunction "1_1") (pintype "passive"))
      (node (ref "R2") (pin "1") (pinfunction "1_1") (pintype "passive"))
      (node (ref "R2-USB") (pin "2") (pinfunction "2_2") (pintype "passive"))
      (node (ref "R2-USB1") (pin "1") (pinfunction "1_1") (pintype "passive"))
      (node (ref "R2_BAT") (pin "1") (pinfunction "1_1") (pintype "passive"))
      (node (ref "R4") (pin "1") (pinfunction "1_1") (pintype "passive"))
      (node (ref "RESET_BUTTON") (pin "1") (pinfunction "1_1") (pintype "passive"))
      (node (ref "RESET_BUTTON") (pin "2") (pinfunction "2_2") (pintype "passive"))
      (node (ref "SENSOR2") (pin "1") (pinfunction "GND_1") (pintype "power_in"))
      (node (ref "SENSOR2") (pin "5") (pinfunction "SDO_5") (pintype "bidirectional"))
      (node (ref "SENSOR2") (pin "7") (pinfunction "GND_7") (pintype "power_in"))
      (node (ref "SJ1") (pin "1") (pinfunction "1_1") (pintype "passive"))
      (node (ref "TPGND") (pin "TP") (pinfunction "TP_TP") (pintype "input"))
      (node (ref "TPGND1") (pin "TP") (pinfunction "TP_TP") (pintype "input"))
      (node (ref "U1") (pin "4") (pinfunction "GND_4") (pintype "power_in"))
      (node (ref "U1") (pin "9") (pinfunction "EXP_9") (pintype "passive"))
      (node (ref "U2") (pin "1") (pinfunction "GND_1") (pintype "power_in"))
      (node (ref "U2") (pin "28") (pinfunction "GND_28") (pintype "power_in"))
      (node (ref "U2") (pin "29_1") (pinfunction "GND_29_1") (pintype "power_in"))
      (node (ref "U2") (pin "29_2") (pinfunction "GND_29_2") (pintype "power_in"))
      (node (ref "U2") (pin "29_3") (pinfunction "GND_29_3") (pintype "power_in"))
      (node (ref "U2") (pin "29_4") (pinfunction "GND_29_4") (pintype "power_in"))
      (node (ref "U2") (pin "29_5") (pinfunction "GND_29_5") (pintype "power_in"))
      (node (ref "U2") (pin "29_6") (pinfunction "GND_29_6") (pintype "power_in"))
      (node (ref "U2") (pin "29_7") (pinfunction "GND_29_7") (pintype "power_in"))
      (node (ref "U2") (pin "29_8") (pinfunction "GND_29_8") (pintype "power_in"))
      (node (ref "U2") (pin "29_9") (pinfunction "GND_29_9") (pintype "power_in"))
      (node (ref "U3") (pin "13") (pinfunction "GND_13") (pintype "power_in"))
      (node (ref "U4") (pin "1") (pinfunction "CTG_1") (pintype "power_in"))
      (node (ref "U4") (pin "4") (pinfunction "GND_4") (pintype "power_in"))
      (node (ref "U4") (pin "6") (pinfunction "QSTRT_6") (pintype "input"))
      (node (ref "U4") (pin "9") (pinfunction "EP_9") (pintype "power_in"))
    )
    (net (code "14") (name "GPIO8") (class "Default")
      (node (ref "R1") (pin "1") (pinfunction "1_1") (pintype "passive"))
      (node (ref "U2") (pin "10") (pinfunction "IO8_10") (pintype "bidirectional"))
    )
    (net (code "15") (name "I2C_PW") (class "Default")
      (node (ref "C1") (pin "1") (pinfunction "1_1") (pintype "passive"))
      (node (ref "C2") (pin "1") (pinfunction "1_1") (pintype "passive"))
      (node (ref "R1_PINH") (pin "2") (pinfunction "2_2") (pintype "passive"))
      (node (ref "R2_PINH") (pin "2") (pinfunction "2_2") (pintype "passive"))
      (node (ref "SENSOR2") (pin "2") (pinfunction "CSB_2") (pintype "input"))
      (node (ref "SENSOR2") (pin "6") (pinfunction "VDDIO_6") (pintype "power_in"))
      (node (ref "SENSOR2") (pin "8") (pinfunction "VDD_8") (pintype "power_in"))
      (node (ref "U2") (pin "17") (pinfunction "IO19_17") (pintype "bidirectional"))
    )
    (net (code "16") (name "INT_RTC") (class "Default")
      (node (ref "R1_PINH1") (pin "1") (pinfunction "1_1") (pintype "passive"))
      (node (ref "TPINTRTC") (pin "TP") (pinfunction "TP_TP") (pintype "input"))
      (node (ref "U2") (pin "8") (pinfunction "IO0_8") (pintype "bidirectional"))
      (node (ref "U3") (pin "3") (pinfunction "SQW/~{INT}_3") (pintype "output"))
    )
    (net (code "17") (name "IO{slash}BOOT") (class "Default")
      (node (ref "BOOT_BUTTON") (pin "3") (pinfunction "3_3") (pintype "passive"))
      (node (ref "BOOT_BUTTON") (pin "4") (pinfunction "4_4") (pintype "passive"))
      (node (ref "C6") (pin "1") (pinfunction "1_1") (pintype "passive"))
      (node (ref "R_BOOT") (pin "1") (pinfunction "1_1") (pintype "passive"))
      (node (ref "U2") (pin "15") (pinfunction "IO9_15") (pintype "bidirectional"))
    )
    (net (code "18") (name "IO{slash}CHANGE") (class "Default")
      (node (ref "C10") (pin "1") (pinfunction "1_1") (pintype "passive"))
      (node (ref "CHANGE_BUTTON") (pin "3") (pinfunction "3_3") (pintype "passive"))
      (node (ref "CHANGE_BUTTON") (pin "4") (pinfunction "4_4") (pintype "passive"))
      (node (ref "R_CHANGE") (pin "1") (pinfunction "1_1") (pintype "passive"))
      (node (ref "U2") (pin "23") (pinfunction "IO15_23") (pintype "bidirectional"))
    )
    (net (code "19") (name "MISO") (class "Default")
      (node (ref "D6") (pin "2") (pinfunction "2_2") (pintype "passive"))
      (node (ref "J4") (pin "P7") (pinfunction "DAT0_P7") (pintype "bidirectional"))
      (node (ref "R5") (pin "1") (pinfunction "1_1") (pintype "passive"))
      (node (ref "TPMISO") (pin "TP") (pinfunction "TP_TP") (pintype "input"))
      (node (ref "U1") (pin "2") (pinfunction "DO(IO1)_2") (pintype "bidirectional"))
      (node (ref "U2") (pin "27") (pinfunction "IO2_27") (pintype "bidirectional"))
    )
    (net (code "20") (name "MOSI") (class "Default")
      (node (ref "D8") (pin "2") (pinfunction "2_2") (pintype "passive"))
      (node (ref "J1") (pin "14") (pinfunction "14_14") (pintype "bidirectional"))
      (node (ref "J4") (pin "P3") (pinfunction "CMD_P3") (pintype "bidirectional"))
      (node (ref "R6") (pin "1") (pinfunction "1_1") (pintype "passive"))
      (node (ref "TPMOSI") (pin "TP") (pinfunction "TP_TP") (pintype "input"))
      (node (ref "U1") (pin "5") (pinfunction "DI(IO0)_5") (pintype "bidirectional"))
      (node (ref "U2") (pin "7") (pinfunction "IO7_7") (pintype "bidirectional"))
    )
    (net (code "21") (name "Net-(CHG_LED-PadC)") (class "Default")
      (node (ref "CHG_LED") (pin "C") (pinfunction "C_C") (pintype "passive"))
      (node (ref "R1_BAT") (pin "1") (pinfunction "1_1") (pintype "passive"))
    )
    (net (code "22") (name "Net-(D2-CATHODE)") (class "Default")
      (node (ref "C1_BAT1") (pin "1") (pinfunction "1_1") (pintype "passive"))
      (node (ref "D2") (pin "1") (pinfunction "CATHODE_1") (pintype "bidirectional"))
      (node (ref "IC4") (pin "1") (pinfunction "VIN_1") (pintype "bidirectional"))
      (node (ref "IC4") (pin "3") (pinfunction "CE_3") (pintype "bidirectional"))
      (node (ref "Q1") (pin "2") (pinfunction "S_2") (pintype "bidirectional"))
    )
    (net (code "23") (name "Net-(D3-A)") (class "Default")
      (node (ref "C4") (pin "1") (pinfunction "1_1") (pintype "passive"))
      (node (ref "D3") (pin "2") (pinfunction "A_2") (pintype "bidirectional"))
      (node (ref "D4") (pin "1") (pinfunction "K_1") (pintype "bidirectional"))
    )
    (net (code "24") (name "Net-(D7-CATHODE)") (class "Default")
      (node (ref "D7") (pin "1") (pinfunction "CATHODE_1") (pintype "bidirectional"))
      (node (ref "R_CAPACITOR") (pin "1") (pinfunction "1_1") (pintype "passive"))
    )
    (net (code "25") (name "Net-(EPD_C1-Pad2)") (class "Default")
      (node (ref "EPD_C1") (pin "2") (pinfunction "2_2") (pintype "passive"))
      (node (ref "J1") (pin "4") (pinfunction "4_4") (pintype "bidirectional"))
    )
    (net (code "26") (name "Net-(EPD_C2-Pad2)") (class "Default")
      (node (ref "EPD_C2") (pin "2") (pinfunction "2_2") (pintype "passive"))
      (node (ref "J1") (pin "5") (pinfunction "5_5") (pintype "bidirectional"))
    )
    (net (code "27") (name "Net-(EPD_C6-Pad2)") (class "Default")
      (node (ref "EPD_C6") (pin "2") (pinfunction "2_2") (pintype "passive"))
      (node (ref "J1") (pin "18") (pinfunction "18_18") (pintype "bidirectional"))
    )
    (net (code "28") (name "Net-(EPD_C7-Pad2)") (class "Default")
      (node (ref "EPD_C7") (pin "2") (pinfunction "2_2") (pintype "passive"))
      (node (ref "J1") (pin "19") (pinfunction "19_19") (pintype "bidirectional"))
    )
    (net (code "29") (name "Net-(EPD_C8-Pad2)") (class "Default")
      (node (ref "EPD_C8") (pin "2") (pinfunction "2_2") (pintype "passive"))
      (node (ref "J1") (pin "20") (pinfunction "20_20") (pintype "bidirectional"))
    )
    (net (code "30") (name "Net-(EPD_C10-Pad2)") (class "Default")
      (node (ref "EPD_C10") (pin "2") (pinfunction "2_2") (pintype "passive"))
      (node (ref "J1") (pin "22") (pinfunction "22_22") (pintype "bidirectional"))
    )
    (net (code "31") (name "Net-(EPD_C12-Pad2)") (class "Default")
      (node (ref "EPD_C12") (pin "2") (pinfunction "2_2") (pintype "passive"))
      (node (ref "J1") (pin "24") (pinfunction "24_24") (pintype "bidirectional"))
    )
    (net (code "32") (name "Net-(IC1-CT)") (class "Default")
      (node (ref "C_DELAY") (pin "1") (pinfunction "1_1") (pintype "passive"))
      (node (ref "IC1") (pin "5") (pinfunction "CT_5") (pintype "bidirectional"))
    )
    (net (code "33") (name "Net-(J2-PadA5)") (class "Default")
      (node (ref "J2") (pin "A5") (pinfunction "A5_A5") (pintype "bidirectional"))
      (node (ref "R2-USB1") (pin "2") (pinfunction "2_2") (pintype "passive"))
    )
    (net (code "34") (name "Net-(J2-PadB5)") (class "Default")
      (node (ref "J2") (pin "B5") (pinfunction "B5_B5") (pintype "bidirectional"))
      (node (ref "R2-USB") (pin "1") (pinfunction "1_1") (pintype "passive"))
    )
    (net (code "35") (name "Net-(MCP73831-PROG)") (class "Default")
      (node (ref "MCP73831") (pin "5") (pinfunction "PROG_5") (pintype "input"))
      (node (ref "R2_BAT") (pin "2") (pinfunction "2_2") (pintype "passive"))
    )
    (net (code "36") (name "Net-(MCP73831-STAT)") (class "Default")
      (node (ref "MCP73831") (pin "1") (pinfunction "STAT_1") (pintype "output"))
      (node (ref "R1_BAT") (pin "2") (pinfunction "2_2") (pintype "passive"))
    )
    (net (code "37") (name "PREVGH") (class "Default")
      (node (ref "D5") (pin "1") (pinfunction "K_1") (pintype "bidirectional"))
      (node (ref "EPD_C9") (pin "2") (pinfunction "2_2") (pintype "passive"))
      (node (ref "J1") (pin "21") (pinfunction "21_21") (pintype "bidirectional"))
    )
    (net (code "38") (name "PREVGL") (class "Default")
      (node (ref "D4") (pin "2") (pinfunction "A_2") (pintype "bidirectional"))
      (node (ref "EPD_C11") (pin "2") (pinfunction "2_2") (pintype "passive"))
      (node (ref "J1") (pin "23") (pinfunction "23_23") (pintype "bidirectional"))
    )
    (net (code "39") (name "RESE") (class "Default")
      (node (ref "J1") (pin "3") (pinfunction "3_3") (pintype "bidirectional"))
      (node (ref "Q3") (pin "2") (pinfunction "S_2") (pintype "bidirectional"))
      (node (ref "R3") (pin "2") (pinfunction "2_2") (pintype "passive"))
    )
    (net (code "40") (name "RESE'") (class "Default")
      (node (ref "R2") (pin "2") (pinfunction "2_2") (pintype "passive"))
      (node (ref "R3") (pin "1") (pinfunction "1_1") (pintype "passive"))
      (node (ref "SJ1") (pin "2") (pinfunction "2_2") (pintype "passive"))
    )
    (net (code "41") (name "RESET") (class "Default")
      (node (ref "C5") (pin "1") (pinfunction "1_1") (pintype "passive"))
      (node (ref "IC1") (pin "1") (pinfunction "VOUT_1") (pintype "bidirectional"))
      (node (ref "RESET_BUTTON") (pin "3") (pinfunction "3_3") (pintype "passive"))
      (node (ref "RESET_BUTTON") (pin "4") (pinfunction "4_4") (pintype "passive"))
      (node (ref "R_RESET") (pin "1") (pinfunction "1_1") (pintype "passive"))
      (node (ref "U2") (pin "3") (pinfunction "EN_3") (pintype "input"))
    )
    (net (code "42") (name "RTC_RST") (class "Default")
      (node (ref "U2") (pin "16") (pinfunction "IO18_16") (pintype "bidirectional"))
      (node (ref "U3") (pin "4") (pinfunction "~{RST}_4") (pintype "input"))
    )
    (net (code "43") (name "RX") (class "Default")
      (node (ref "TPRX") (pin "TP") (pinfunction "TP_TP") (pintype "input"))
      (node (ref "U2") (pin "24") (pinfunction "RXD0/GPIO17_24") (pintype "bidirectional"))
    )
    (net (code "44") (name "SCK") (class "Default")
      (node (ref "D9") (pin "2") (pinfunction "2_2") (pintype "passive"))
      (node (ref "J1") (pin "13") (pinfunction "13_13") (pintype "bidirectional"))
      (node (ref "J4") (pin "P5") (pinfunction "CLK_P5") (pintype "bidirectional"))
      (node (ref "R7") (pin "1") (pinfunction "1_1") (pintype "passive"))
      (node (ref "TPSCK") (pin "TP") (pinfunction "TP_TP") (pintype "input"))
      (node (ref "U1") (pin "6") (pinfunction "CLK_6") (pintype "input"))
      (node (ref "U2") (pin "6") (pinfunction "IO6_6") (pintype "bidirectional"))
    )
    (net (code "45") (name "SCL") (class "Default")
      (node (ref "J3") (pin "4") (pinfunction "4_4") (pintype "passive"))
      (node (ref "R2_PINH") (pin "1") (pinfunction "1_1") (pintype "passive"))
      (node (ref "SENSOR2") (pin "4") (pinfunction "SCK_4") (pintype "input"))
      (node (ref "U2") (pin "20") (pinfunction "IO22_20") (pintype "bidirectional"))
      (node (ref "U3") (pin "16") (pinfunction "SCL_16") (pintype "input"))
      (node (ref "U4") (pin "7") (pinfunction "SCL_7") (pintype "input"))
    )
    (net (code "46") (name "SDA") (class "Default")
      (node (ref "J3") (pin "3") (pinfunction "3_3") (pintype "passive"))
      (node (ref "R1_PINH") (pin "1") (pinfunction "1_1") (pintype "passive"))
      (node (ref "SENSOR2") (pin "3") (pinfunction "SDI_3") (pintype "bidirectional"))
      (node (ref "U2") (pin "19") (pinfunction "IO21_19") (pintype "bidirectional"))
      (node (ref "U3") (pin "15") (pinfunction "SDA_15") (pintype "bidirectional"))
      (node (ref "U4") (pin "8") (pinfunction "SDA_8") (pintype "bidirectional"))
    )
    (net (code "47") (name "SRC") (class "Default")
      (node (ref "C4") (pin "2") (pinfunction "2_2") (pintype "passive"))
      (node (ref "D5") (pin "2") (pinfunction "A_2") (pintype "bidirectional"))
      (node (ref "L1") (pin "2") (pinfunction "2_2") (pintype "passive"))
      (node (ref "Q3") (pin "3") (pinfunction "D_3") (pintype "bidirectional"))
    )
    (net (code "48") (name "SS_SD") (class "Default")
      (node (ref "D12") (pin "2") (pinfunction "2_2") (pintype "passive"))
      (node (ref "J4") (pin "P2") (pinfunction "CD/DAT3_P2") (pintype "bidirectional"))
      (node (ref "R10") (pin "1") (pinfunction "1_1") (pintype "passive"))
      (node (ref "U2") (pin "4") (pinfunction "IO4_4") (pintype "bidirectional"))
    )
    (net (code "49") (name "TX") (class "Default")
      (node (ref "TPTX") (pin "TP") (pinfunction "TP_TP") (pintype "input"))
      (node (ref "U2") (pin "25") (pinfunction "TXD0/GPIO16_25") (pintype "bidirectional"))
    )
    (net (code "50") (name "USB_D+") (class "Default")
      (node (ref "D1") (pin "1") (pinfunction "I/O1_1_1") (pintype "bidirectional"))
      (node (ref "U2") (pin "14") (pinfunction "IO13_14") (pintype "bidirectional"))
    )
    (net (code "51") (name "USB_D-") (class "Default")
      (node (ref "D1") (pin "3") (pinfunction "I/O2_1_3") (pintype "bidirectional"))
      (node (ref "U2") (pin "13") (pinfunction "IO12_13") (pintype "bidirectional"))
    )
    (net (code "52") (name "VBAT") (class "Default")
      (node (ref "C2_BAT") (pin "1") (pinfunction "1_1") (pintype "passive"))
      (node (ref "MCP73831") (pin "3") (pinfunction "VBAT_3") (pintype "power_in"))
      (node (ref "Q1") (pin "3") (pinfunction "D_3") (pintype "bidirectional"))
      (node (ref "TPVBAT") (pin "TP") (pinfunction "TP_TP") (pintype "input"))
      (node (ref "U4") (pin "2") (pinfunction "CELL_2") (pintype "power_in"))
      (node (ref "U4") (pin "3") (pinfunction "VDD_3") (pintype "power_in"))
    )
    (net (code "53") (name "VBUS") (class "Default")
      (node (ref "C1_BAT") (pin "1") (pinfunction "1_1") (pintype "passive"))
      (node (ref "C4_USB") (pin "1") (pinfunction "1_1") (pintype "passive"))
      (node (ref "C5_USB") (pin "1") (pinfunction "1_1") (pintype "passive"))
      (node (ref "CHG_LED") (pin "A") (pinfunction "A_A") (pintype "passive"))
      (node (ref "D1") (pin "5") (pinfunction "VBUS_5") (pintype "bidirectional"))
      (node (ref "D2") (pin "2") (pinfunction "ANODE_2") (pintype "bidirectional"))
      (node (ref "MCP73831") (pin "4") (pinfunction "VIN_4") (pintype "power_in"))
      (node (ref "PFMF.050.1") (pin "2") (pinfunction "2_2") (pintype "passive"))
      (node (ref "Q1") (pin "1") (pinfunction "G_1") (pintype "bidirectional"))
      (node (ref "R1_PWRUSB") (pin "2") (pinfunction "2_2") (pintype "passive"))
      (node (ref "TPVBUS") (pin "TP") (pinfunction "TP_TP") (pintype "input"))
    )
    (net (code "54") (name "VRTC") (class "Default")
      (node (ref "C11") (pin "1") (pinfunction "1_1") (pintype "passive"))
      (node (ref "C8") (pin "1") (pinfunction "1_1") (pintype "passive"))
      (node (ref "R_CAPACITOR") (pin "2") (pinfunction "2_2") (pintype "passive"))
      (node (ref "U3") (pin "14") (pinfunction "VBAT_14") (pintype "power_in"))
    )
    (net (code "55") (name "VUSB") (class "Default")
      (node (ref "J2") (pin "A4") (pinfunction "A4_A4") (pintype "bidirectional"))
      (node (ref "J2") (pin "A9") (pinfunction "A9_A9") (pintype "bidirectional"))
      (node (ref "J2") (pin "B4") (pinfunction "B4_B4") (pintype "bidirectional"))
      (node (ref "J2") (pin "B9") (pinfunction "B9_B9") (pintype "bidirectional"))
      (node (ref "PFMF.050.1") (pin "1") (pinfunction "1_1") (pintype "passive"))
    )
    (net (code "56") (name "unconnected-(IC1-NC-Pad4)") (class "Default")
      (node (ref "IC1") (pin "4") (pinfunction "NC_4") (pintype "no_connect"))
    )
    (net (code "57") (name "unconnected-(IC4-NC-Pad4)") (class "Default")
      (node (ref "IC4") (pin "4") (pinfunction "NC_4") (pintype "no_connect"))
    )
    (net (code "58") (name "unconnected-(J1-Pad1)") (class "Default")
      (node (ref "J1") (pin "1") (pinfunction "1_1") (pintype "bidirectional"))
    )
    (net (code "59") (name "unconnected-(J1-Pad6)") (class "Default")
      (node (ref "J1") (pin "6") (pinfunction "6_6") (pintype "bidirectional"))
    )
    (net (code "60") (name "unconnected-(J1-Pad7)") (class "Default")
      (node (ref "J1") (pin "7") (pinfunction "7_7") (pintype "bidirectional"))
    )
    (net (code "61") (name "unconnected-(J2-PadA8)") (class "Default")
      (node (ref "J2") (pin "A8") (pinfunction "A8_A8") (pintype "bidirectional"))
    )
    (net (code "62") (name "unconnected-(J2-PadB8)") (class "Default")
      (node (ref "J2") (pin "B8") (pinfunction "B8_B8") (pintype "bidirectional"))
    )
    (net (code "63") (name "unconnected-(J4-DAT1-PadP8)") (class "Default")
      (node (ref "J4") (pin "P8") (pinfunction "DAT1_P8") (pintype "bidirectional"))
    )
    (net (code "64") (name "unconnected-(J4-DAT2-PadP1)") (class "Default")
      (node (ref "J4") (pin "P1") (pinfunction "DAT2_P1") (pintype "bidirectional"))
    )
    (net (code "65") (name "unconnected-(J4-DETECTION_1-PadS1)") (class "Default")
      (node (ref "J4") (pin "S1") (pinfunction "DETECTION_1_S1") (pintype "bidirectional"))
    )
    (net (code "66") (name "unconnected-(J4-DETECTION_2-PadS2)") (class "Default")
      (node (ref "J4") (pin "S2") (pinfunction "DETECTION_2_S2") (pintype "bidirectional"))
    )
    (net (code "67") (name "unconnected-(U2-NC-Pad22)") (class "Default")
      (node (ref "U2") (pin "22") (pinfunction "NC_22") (pintype "no_connect"))
    )
    (net (code "68") (name "unconnected-(U4-~{ALERT}-Pad5)") (class "Default")
      (node (ref "U4") (pin "5") (pinfunction "~{ALERT}_5") (pintype "output"))
    )
  )
)
